# ProPrj_ftdi-jtag-xilinx_2025-03-20_v3_2.net
KiCad netlist of a schematic drawn in EasyEDA Pro
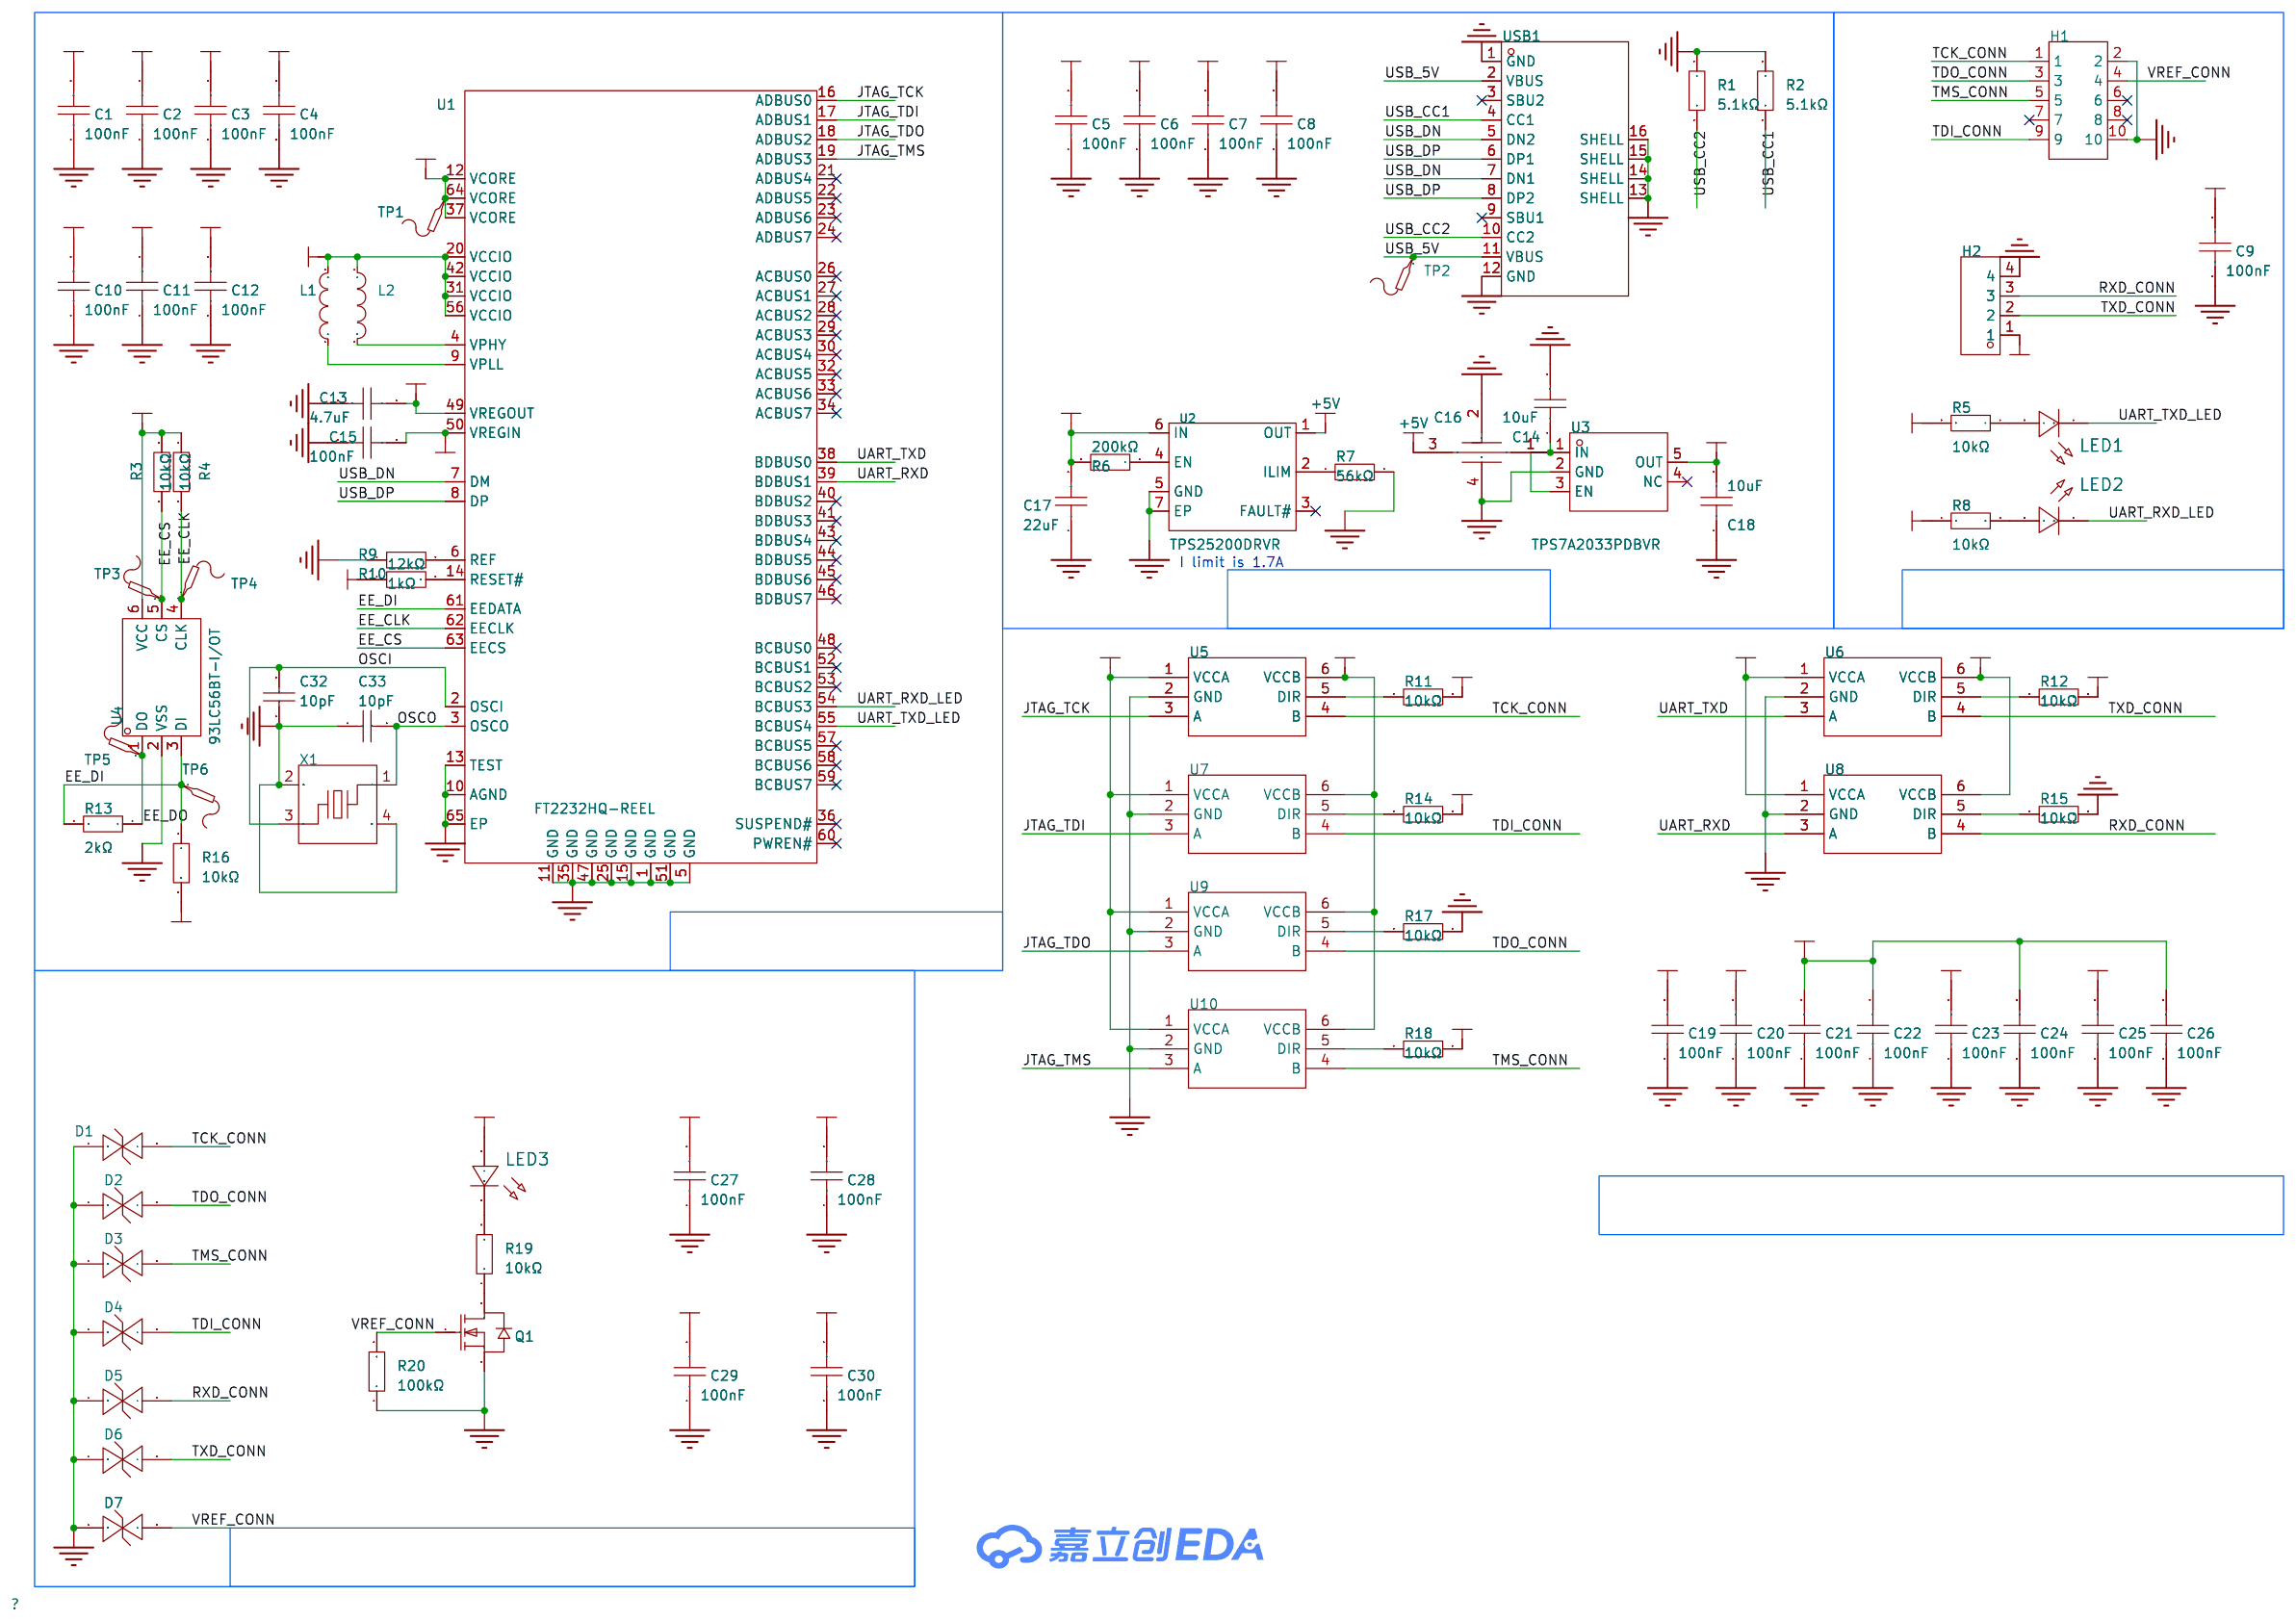
[diagram p0: schematic sheet]

(export (version "E")
  (design (tool "Eeschema 10.0.6"))
  (components
    (comp (ref "C1")
      (value "100nF")
      (footprint "easyedapro:C0603")
      (fields
        (field (name "Manufacturer Part") "CC0402KRX7R7BB104")
        (field (name "Manufacturer") "YAGEO(国巨)")
      )
      (libsource (lib "easyedapro") (part "CapAcitance"))
    )
    (comp (ref "C2")
      (value "100nF")
      (footprint "easyedapro:C0603")
      (fields
        (field (name "Manufacturer Part") "CC0402KRX7R7BB104")
        (field (name "Manufacturer") "YAGEO(国巨)")
      )
      (libsource (lib "easyedapro") (part "CapAcitance"))
    )
    (comp (ref "C3")
      (value "100nF")
      (footprint "easyedapro:C0603")
      (fields
        (field (name "Manufacturer Part") "CC0402KRX7R7BB104")
        (field (name "Manufacturer") "YAGEO(国巨)")
      )
      (libsource (lib "easyedapro") (part "CapAcitance"))
    )
    (comp (ref "C4")
      (value "100nF")
      (footprint "easyedapro:C0603")
      (fields
        (field (name "Manufacturer Part") "CC0402KRX7R7BB104")
        (field (name "Manufacturer") "YAGEO(国巨)")
      )
      (libsource (lib "easyedapro") (part "CapAcitance"))
    )
    (comp (ref "C5")
      (value "100nF")
      (footprint "easyedapro:C0603")
      (fields
        (field (name "Manufacturer Part") "CC0402KRX7R7BB104")
        (field (name "Manufacturer") "YAGEO(国巨)")
      )
      (libsource (lib "easyedapro") (part "CapAcitance"))
    )
    (comp (ref "C6")
      (value "100nF")
      (footprint "easyedapro:C0603")
      (fields
        (field (name "Manufacturer Part") "CC0402KRX7R7BB104")
        (field (name "Manufacturer") "YAGEO(国巨)")
      )
      (libsource (lib "easyedapro") (part "CapAcitance"))
    )
    (comp (ref "C7")
      (value "100nF")
      (footprint "easyedapro:C0603")
      (fields
        (field (name "Manufacturer Part") "CC0402KRX7R7BB104")
        (field (name "Manufacturer") "YAGEO(国巨)")
      )
      (libsource (lib "easyedapro") (part "CapAcitance"))
    )
    (comp (ref "C8")
      (value "100nF")
      (footprint "easyedapro:C0603")
      (fields
        (field (name "Manufacturer Part") "CC0402KRX7R7BB104")
        (field (name "Manufacturer") "YAGEO(国巨)")
      )
      (libsource (lib "easyedapro") (part "CapAcitance"))
    )
    (comp (ref "C9")
      (value "100nF")
      (footprint "easyedapro:C0603")
      (fields
        (field (name "Manufacturer Part") "CC0402KRX7R7BB104")
        (field (name "Manufacturer") "YAGEO(国巨)")
      )
      (libsource (lib "easyedapro") (part "CapAcitance"))
    )
    (comp (ref "C10")
      (value "100nF")
      (footprint "easyedapro:C0603")
      (fields
        (field (name "Manufacturer Part") "CC0402KRX7R7BB104")
        (field (name "Manufacturer") "YAGEO(国巨)")
      )
      (libsource (lib "easyedapro") (part "CapAcitance"))
    )
    (comp (ref "C11")
      (value "100nF")
      (footprint "easyedapro:C0603")
      (fields
        (field (name "Manufacturer Part") "CC0402KRX7R7BB104")
        (field (name "Manufacturer") "YAGEO(国巨)")
      )
      (libsource (lib "easyedapro") (part "CapAcitance"))
    )
    (comp (ref "C12")
      (value "100nF")
      (footprint "easyedapro:C0603")
      (fields
        (field (name "Manufacturer Part") "CC0402KRX7R7BB104")
        (field (name "Manufacturer") "YAGEO(国巨)")
      )
      (libsource (lib "easyedapro") (part "CapAcitance"))
    )
    (comp (ref "C13")
      (value "4.7uF")
      (footprint "easyedapro:C0603")
      (fields
        (field (name "Manufacturer Part") "CL05A475KP5NRNC")
        (field (name "Manufacturer") "SAMSUNG(三星)")
      )
      (libsource (lib "easyedapro") (part "CapAcitance"))
    )
    (comp (ref "C14")
      (value "10uF")
      (footprint "easyedapro:C0603")
      (fields
        (field (name "Manufacturer Part") "CL10A106MA8NRNC")
        (field (name "Manufacturer") "SAMSUNG(三星)")
      )
      (libsource (lib "easyedapro") (part "CapAcitance"))
    )
    (comp (ref "C15")
      (value "100nF")
      (footprint "easyedapro:C0603")
      (fields
        (field (name "Manufacturer Part") "CC0402KRX7R7BB104")
        (field (name "Manufacturer") "YAGEO(国巨)")
      )
      (libsource (lib "easyedapro") (part "CapAcitance"))
    )
    (comp (ref "C16")
      (value "NFM21PC104R1E3D")
      (footprint "easyedapro:CAP-SMD_4P-L2.0-W1.25")
      (description "电容量:100nF;精度:±20%;直流电阻:30mΩ;")
      (fields (field (name "Manufacturer") "muRata(村田)"))
      (libsource (lib "easyedapro") (part "NFM21PC104R1E3D"))
    )
    (comp (ref "C17")
      (value "22uF")
      (footprint "easyedapro:C0603")
      (fields
        (field (name "Manufacturer Part") "CGA0805X5R226M350MT")
        (field (name "Manufacturer") "HRE(芯声)")
      )
      (libsource (lib "easyedapro") (part "CapAcitance"))
    )
    (comp (ref "C18")
      (value "10uF")
      (footprint "easyedapro:C0603")
      (fields
        (field (name "Manufacturer Part") "CL10A106MA8NRNC")
        (field (name "Manufacturer") "SAMSUNG(三星)")
      )
      (libsource (lib "easyedapro") (part "CapAcitance"))
    )
    (comp (ref "C19")
      (value "100nF")
      (footprint "easyedapro:C0603")
      (fields
        (field (name "Manufacturer Part") "CC0402KRX7R7BB104")
        (field (name "Manufacturer") "YAGEO(国巨)")
      )
      (libsource (lib "easyedapro") (part "CapAcitance"))
    )
    (comp (ref "C20")
      (value "100nF")
      (footprint "easyedapro:C0603")
      (fields
        (field (name "Manufacturer Part") "CC0402KRX7R7BB104")
        (field (name "Manufacturer") "YAGEO(国巨)")
      )
      (libsource (lib "easyedapro") (part "CapAcitance"))
    )
    (comp (ref "C21")
      (value "100nF")
      (footprint "easyedapro:C0603")
      (fields
        (field (name "Manufacturer Part") "CC0402KRX7R7BB104")
        (field (name "Manufacturer") "YAGEO(国巨)")
      )
      (libsource (lib "easyedapro") (part "CapAcitance"))
    )
    (comp (ref "C22")
      (value "100nF")
      (footprint "easyedapro:C0603")
      (fields
        (field (name "Manufacturer Part") "CC0402KRX7R7BB104")
        (field (name "Manufacturer") "YAGEO(国巨)")
      )
      (libsource (lib "easyedapro") (part "CapAcitance"))
    )
    (comp (ref "C23")
      (value "100nF")
      (footprint "easyedapro:C0603")
      (fields
        (field (name "Manufacturer Part") "CC0402KRX7R7BB104")
        (field (name "Manufacturer") "YAGEO(国巨)")
      )
      (libsource (lib "easyedapro") (part "CapAcitance"))
    )
    (comp (ref "C24")
      (value "100nF")
      (footprint "easyedapro:C0603")
      (fields
        (field (name "Manufacturer Part") "CC0402KRX7R7BB104")
        (field (name "Manufacturer") "YAGEO(国巨)")
      )
      (libsource (lib "easyedapro") (part "CapAcitance"))
    )
    (comp (ref "C25")
      (value "100nF")
      (footprint "easyedapro:C0603")
      (fields
        (field (name "Manufacturer Part") "CC0402KRX7R7BB104")
        (field (name "Manufacturer") "YAGEO(国巨)")
      )
      (libsource (lib "easyedapro") (part "CapAcitance"))
    )
    (comp (ref "C26")
      (value "100nF")
      (footprint "easyedapro:C0603")
      (fields
        (field (name "Manufacturer Part") "CC0402KRX7R7BB104")
        (field (name "Manufacturer") "YAGEO(国巨)")
      )
      (libsource (lib "easyedapro") (part "CapAcitance"))
    )
    (comp (ref "C27")
      (value "100nF")
      (footprint "easyedapro:C0603")
      (fields
        (field (name "Manufacturer Part") "CC0402KRX7R7BB104")
        (field (name "Manufacturer") "YAGEO(国巨)")
      )
      (libsource (lib "easyedapro") (part "CapAcitance"))
    )
    (comp (ref "C28")
      (value "100nF")
      (footprint "easyedapro:C0603")
      (fields
        (field (name "Manufacturer Part") "CC0402KRX7R7BB104")
        (field (name "Manufacturer") "YAGEO(国巨)")
      )
      (libsource (lib "easyedapro") (part "CapAcitance"))
    )
    (comp (ref "C29")
      (value "100nF")
      (footprint "easyedapro:C0603")
      (fields
        (field (name "Manufacturer Part") "CC0402KRX7R7BB104")
        (field (name "Manufacturer") "YAGEO(国巨)")
      )
      (libsource (lib "easyedapro") (part "CapAcitance"))
    )
    (comp (ref "C30")
      (value "100nF")
      (footprint "easyedapro:C0603")
      (fields
        (field (name "Manufacturer Part") "CC0402KRX7R7BB104")
        (field (name "Manufacturer") "YAGEO(国巨)")
      )
      (libsource (lib "easyedapro") (part "CapAcitance"))
    )
    (comp (ref "C32")
      (value "10pF")
      (footprint "easyedapro:C0402")
      (description "容值:10pF;精度:±5%;额定电压:50V;材质(温度系数):NP0;")
      (fields
        (field (name "Manufacturer Part") "CC0402JRNPO9BN100")
        (field (name "Manufacturer") "YAGEO(国巨)")
      )
      (libsource (lib "easyedapro") (part "CC0402JRNPO9BN100"))
    )
    (comp (ref "C33")
      (value "10pF")
      (footprint "easyedapro:C0402")
      (description "容值:10pF;精度:±5%;额定电压:50V;材质(温度系数):NP0;")
      (fields
        (field (name "Manufacturer Part") "CC0402JRNPO9BN100")
        (field (name "Manufacturer") "YAGEO(国巨)")
      )
      (libsource (lib "easyedapro") (part "CC0402JRNPO9BN100"))
    )
    (comp (ref "D1")
      (value "H5VL10B")
      (footprint "easyedapro:SOD-882_L1.0-W0.6-BI")
      (description "极性:双向;反向截止电压(Vrwm):5V;最大钳位电压:10V;峰值脉冲电流(Ipp):5A;峰值脉冲功率(Ppp):50W;击穿电压:5.6V;")
      (fields (field (name "Manufacturer") "宏迦橙"))
      (libsource (lib "easyedapro") (part "H5VL10B"))
    )
    (comp (ref "D2")
      (value "H5VL10B")
      (footprint "easyedapro:SOD-882_L1.0-W0.6-BI")
      (description "极性:双向;反向截止电压(Vrwm):5V;最大钳位电压:10V;峰值脉冲电流(Ipp):5A;峰值脉冲功率(Ppp):50W;击穿电压:5.6V;")
      (fields (field (name "Manufacturer") "宏迦橙"))
      (libsource (lib "easyedapro") (part "H5VL10B"))
    )
    (comp (ref "D3")
      (value "H5VL10B")
      (footprint "easyedapro:SOD-882_L1.0-W0.6-BI")
      (description "极性:双向;反向截止电压(Vrwm):5V;最大钳位电压:10V;峰值脉冲电流(Ipp):5A;峰值脉冲功率(Ppp):50W;击穿电压:5.6V;")
      (fields (field (name "Manufacturer") "宏迦橙"))
      (libsource (lib "easyedapro") (part "H5VL10B"))
    )
    (comp (ref "D4")
      (value "H5VL10B")
      (footprint "easyedapro:SOD-882_L1.0-W0.6-BI")
      (description "极性:双向;反向截止电压(Vrwm):5V;最大钳位电压:10V;峰值脉冲电流(Ipp):5A;峰值脉冲功率(Ppp):50W;击穿电压:5.6V;")
      (fields (field (name "Manufacturer") "宏迦橙"))
      (libsource (lib "easyedapro") (part "H5VL10B"))
    )
    (comp (ref "D5")
      (value "H5VL10B")
      (footprint "easyedapro:SOD-882_L1.0-W0.6-BI")
      (description "极性:双向;反向截止电压(Vrwm):5V;最大钳位电压:10V;峰值脉冲电流(Ipp):5A;峰值脉冲功率(Ppp):50W;击穿电压:5.6V;")
      (fields (field (name "Manufacturer") "宏迦橙"))
      (libsource (lib "easyedapro") (part "H5VL10B"))
    )
    (comp (ref "D6")
      (value "H5VL10B")
      (footprint "easyedapro:SOD-882_L1.0-W0.6-BI")
      (description "极性:双向;反向截止电压(Vrwm):5V;最大钳位电压:10V;峰值脉冲电流(Ipp):5A;峰值脉冲功率(Ppp):50W;击穿电压:5.6V;")
      (fields (field (name "Manufacturer") "宏迦橙"))
      (libsource (lib "easyedapro") (part "H5VL10B"))
    )
    (comp (ref "D7")
      (value "H5VL10B")
      (footprint "easyedapro:SOD-882_L1.0-W0.6-BI")
      (description "极性:双向;反向截止电压(Vrwm):5V;最大钳位电压:10V;峰值脉冲电流(Ipp):5A;峰值脉冲功率(Ppp):50W;击穿电压:5.6V;")
      (fields (field (name "Manufacturer") "宏迦橙"))
      (libsource (lib "easyedapro") (part "H5VL10B"))
    )
    (comp (ref "H1")
      (value "PZ254-2-05-Z-8.5")
      (footprint "easyedapro:HDR-TH_10P-P2.54-V-M-R2-C5-S2.54")
      (fields (field (name "Manufacturer") "HCTL(华灿天禄)"))
      (libsource (lib "easyedapro") (part "PZ254-2-05-Z-8.5"))
    )
    (comp (ref "H2")
      (value "PZ254V-11-04P")
      (footprint "easyedapro:HDR-TH_4P-P2.54-V-M")
      (fields (field (name "Manufacturer") "XFCN(兴飞)"))
      (libsource (lib "easyedapro") (part "PZ254V-11-04P_C2691448"))
    )
    (comp (ref "L1")
      (value "BLM15PD121SN1D")
      (footprint "easyedapro:L0402")
      (description "标称阻抗@测试频率:120Ω@100MHz;误差:±25%;直流电阻(RDC):90mΩ;")
      (fields (field (name "Manufacturer") "muRata(村田)"))
      (libsource (lib "easyedapro") (part "BLM15PD121SN1D"))
    )
    (comp (ref "L2")
      (value "BLM15PD121SN1D")
      (footprint "easyedapro:L0402")
      (description "标称阻抗@测试频率:120Ω@100MHz;误差:±25%;直流电阻(RDC):90mΩ;")
      (fields (field (name "Manufacturer") "muRata(村田)"))
      (libsource (lib "easyedapro") (part "BLM15PD121SN1D"))
    )
    (comp (ref "LED1")
      (value "NCD0603Y1")
      (footprint "easyedapro:LED_0603")
      (fields (field (name "Manufacturer") "国星光电"))
      (libsource (lib "easyedapro") (part "LED_R"))
    )
    (comp (ref "LED2")
      (value "NCD0603Y1")
      (footprint "easyedapro:LED_0603")
      (fields (field (name "Manufacturer") "国星光电"))
      (libsource (lib "easyedapro") (part "LED_R"))
    )
    (comp (ref "LED3")
      (value "NCD0603Y1")
      (footprint "easyedapro:LED_0603")
      (fields (field (name "Manufacturer") "国星光电"))
      (libsource (lib "easyedapro") (part "LED_R"))
    )
    (comp (ref "Q1")
      (value "SI2302")
      (footprint "easyedapro:SOT-23-3_L2.9-W1.3-P1.90-LS2.4-BR")
      (description "类型:1个N沟道;漏源电压(Vdss):20V;连续漏极电流(Id):3A;导通电阻(RDS(on)):50mΩ@4.5V,3A;耗散功率(Pd):1W;阈值电压(Vgs(th)):1V;")
      (fields (field (name "Manufacturer") "YONGYUTAI(永裕泰)"))
      (libsource (lib "easyedapro") (part "SI2302_C2891732"))
    )
    (comp (ref "R1")
      (value "5.1kΩ")
      (footprint "easyedapro:R0603")
      (fields
        (field (name "Manufacturer Part") "0402WGF5101TCE")
        (field (name "Manufacturer") "UNI-ROYAL(厚声)")
      )
      (libsource (lib "easyedapro") (part "电阻"))
    )
    (comp (ref "R2")
      (value "5.1kΩ")
      (footprint "easyedapro:R0603")
      (fields
        (field (name "Manufacturer Part") "0402WGF5101TCE")
        (field (name "Manufacturer") "UNI-ROYAL(厚声)")
      )
      (libsource (lib "easyedapro") (part "电阻"))
    )
    (comp (ref "R3")
      (value "10kΩ")
      (footprint "easyedapro:R0603")
      (fields (field (name "Manufacturer Part") "RC0402FR-0710KL") (field (name "Manufacturer") "YAGEO(国巨)"))
      (libsource (lib "easyedapro") (part "电阻"))
    )
    (comp (ref "R4")
      (value "10kΩ")
      (footprint "easyedapro:R0603")
      (fields (field (name "Manufacturer Part") "RC0402FR-0710KL") (field (name "Manufacturer") "YAGEO(国巨)"))
      (libsource (lib "easyedapro") (part "电阻"))
    )
    (comp (ref "R5")
      (value "10kΩ")
      (footprint "easyedapro:R0603")
      (fields (field (name "Manufacturer Part") "RC0402FR-0710KL") (field (name "Manufacturer") "YAGEO(国巨)"))
      (libsource (lib "easyedapro") (part "电阻"))
    )
    (comp (ref "R6")
      (value "200kΩ")
      (footprint "easyedapro:R0603")
      (fields
        (field (name "Manufacturer Part") "0402WGF2003TCE")
        (field (name "Manufacturer") "UNI-ROYAL(厚声)")
      )
      (libsource (lib "easyedapro") (part "电阻"))
    )
    (comp (ref "R7")
      (value "56kΩ")
      (footprint "easyedapro:R0603")
      (fields
        (field (name "Manufacturer Part") "0402WGF5602TCE")
        (field (name "Manufacturer") "UNI-ROYAL(厚声)")
      )
      (libsource (lib "easyedapro") (part "电阻"))
    )
    (comp (ref "R8")
      (value "10kΩ")
      (footprint "easyedapro:R0603")
      (fields (field (name "Manufacturer Part") "RC0402FR-0710KL") (field (name "Manufacturer") "YAGEO(国巨)"))
      (libsource (lib "easyedapro") (part "电阻"))
    )
    (comp (ref "R9")
      (value "12kΩ")
      (footprint "easyedapro:R0603")
      (fields
        (field (name "Manufacturer Part") "0402WGF1202TCE")
        (field (name "Manufacturer") "UNI-ROYAL(厚声)")
      )
      (libsource (lib "easyedapro") (part "电阻"))
    )
    (comp (ref "R10")
      (value "1kΩ")
      (footprint "easyedapro:R0603")
      (fields
        (field (name "Manufacturer Part") "0402WGF1001TCE")
        (field (name "Manufacturer") "UNI-ROYAL(厚声)")
      )
      (libsource (lib "easyedapro") (part "电阻"))
    )
    (comp (ref "R11")
      (value "10kΩ")
      (footprint "easyedapro:R0603")
      (fields (field (name "Manufacturer Part") "RC0402FR-0710KL") (field (name "Manufacturer") "YAGEO(国巨)"))
      (libsource (lib "easyedapro") (part "电阻"))
    )
    (comp (ref "R12")
      (value "10kΩ")
      (footprint "easyedapro:R0603")
      (fields (field (name "Manufacturer Part") "RC0402FR-0710KL") (field (name "Manufacturer") "YAGEO(国巨)"))
      (libsource (lib "easyedapro") (part "电阻"))
    )
    (comp (ref "R13")
      (value "2kΩ")
      (footprint "easyedapro:R0603")
      (fields (field (name "Manufacturer Part") "FRC0402F2001TS") (field (name "Manufacturer") "FOJAN(富捷)"))
      (libsource (lib "easyedapro") (part "电阻"))
    )
    (comp (ref "R14")
      (value "10kΩ")
      (footprint "easyedapro:R0603")
      (fields (field (name "Manufacturer Part") "RC0402FR-0710KL") (field (name "Manufacturer") "YAGEO(国巨)"))
      (libsource (lib "easyedapro") (part "电阻"))
    )
    (comp (ref "R15")
      (value "10kΩ")
      (footprint "easyedapro:R0603")
      (fields (field (name "Manufacturer Part") "RC0402FR-0710KL") (field (name "Manufacturer") "YAGEO(国巨)"))
      (libsource (lib "easyedapro") (part "电阻"))
    )
    (comp (ref "R16")
      (value "10kΩ")
      (footprint "easyedapro:R0603")
      (fields (field (name "Manufacturer Part") "RC0402FR-0710KL") (field (name "Manufacturer") "YAGEO(国巨)"))
      (libsource (lib "easyedapro") (part "电阻"))
    )
    (comp (ref "R17")
      (value "10kΩ")
      (footprint "easyedapro:R0603")
      (fields (field (name "Manufacturer Part") "RC0402FR-0710KL") (field (name "Manufacturer") "YAGEO(国巨)"))
      (libsource (lib "easyedapro") (part "电阻"))
    )
    (comp (ref "R18")
      (value "10kΩ")
      (footprint "easyedapro:R0603")
      (fields (field (name "Manufacturer Part") "RC0402FR-0710KL") (field (name "Manufacturer") "YAGEO(国巨)"))
      (libsource (lib "easyedapro") (part "电阻"))
    )
    (comp (ref "R19")
      (value "10kΩ")
      (footprint "easyedapro:R0603")
      (fields (field (name "Manufacturer Part") "RC0402FR-0710KL") (field (name "Manufacturer") "YAGEO(国巨)"))
      (libsource (lib "easyedapro") (part "电阻"))
    )
    (comp (ref "R20")
      (value "100kΩ")
      (footprint "easyedapro:R0402")
      (description "电阻类型:厚膜电阻;阻值:100kΩ;精度:±1%;功率:62.5mW;最大工作电压:50V;温度系数:±100ppm/°C;")
      (fields
        (field (name "Manufacturer Part") "0402WGF1003TCE")
        (field (name "Manufacturer") "UNI-ROYAL(厚声)")
      )
      (libsource (lib "easyedapro") (part "0402WGF1003TCE"))
    )
    (comp (ref "TP1")
      (value "~")
      (footprint "easyedapro:Test-Point-0.5mm")
      (description "Test Point 测试点")
      (libsource (lib "easyedapro") (part "Test-Point"))
    )
    (comp (ref "TP2")
      (value "~")
      (footprint "easyedapro:Test-Point-0.5mm")
      (description "Test Point 测试点")
      (libsource (lib "easyedapro") (part "Test-Point"))
    )
    (comp (ref "TP3")
      (value "~")
      (footprint "easyedapro:Test-Point-0.5mm")
      (description "Test Point 测试点")
      (libsource (lib "easyedapro") (part "Test-Point"))
    )
    (comp (ref "TP4")
      (value "~")
      (footprint "easyedapro:Test-Point-0.5mm")
      (description "Test Point 测试点")
      (libsource (lib "easyedapro") (part "Test-Point"))
    )
    (comp (ref "TP5")
      (value "~")
      (footprint "easyedapro:Test-Point-0.5mm")
      (description "Test Point 测试点")
      (libsource (lib "easyedapro") (part "Test-Point"))
    )
    (comp (ref "TP6")
      (value "~")
      (footprint "easyedapro:Test-Point-0.5mm")
      (description "Test Point 测试点")
      (libsource (lib "easyedapro") (part "Test-Point"))
    )
    (comp (ref "U1")
      (value "FT2232HQ-REEL")
      (footprint "easyedapro:QFN-64_L9.0-W9.0-P0.50-TL-EP4.3")
      (description "应用功能:USB转UART；USB转FIFO;接口协议:UART;供电电压:3V~3.6V;")
      (fields (field (name "Manufacturer") "FTDI(飞特帝亚)"))
      (libsource (lib "easyedapro") (part "FT2232HQ-REEL"))
    )
    (comp (ref "U2")
      (value "TPS25200DRVR")
      (footprint "easyedapro:WSON-6_L2.0-W2.0-P0.65-TL-EP")
      (description "TPS25200 具有过压钳位的 6.5V/2.8A 电子保险丝")
      (fields (field (name "Manufacturer") "TI(德州仪器)"))
      (libsource (lib "easyedapro") (part "TPS25200DRVR"))
    )
    (comp (ref "U3")
      (value "TPS7A2033PDBVR")
      (footprint "easyedapro:SOT-23-5_L2.9-W1.6-P0.95-LS2.8-BR")
      (fields (field (name "Manufacturer") "TI(德州仪器)"))
      (libsource (lib "easyedapro") (part "TPS7A2033PDBVR"))
    )
    (comp (ref "U4")
      (value "93LC56BT-I/OT")
      (footprint "easyedapro:SOT-23-6_L2.9-W1.6-P0.95-LS2.8-BR")
      (fields (field (name "Manufacturer") "MICROCHIP(美国微芯)"))
      (libsource (lib "easyedapro") (part "93LC56BT-I/OT"))
    )
    (comp (ref "U5")
      (value "SN74LVC1T45DBVR")
      (footprint "easyedapro:SOT-23-6_L2.9-W1.6-P0.95-LS2.8-BR")
      (description "数据速率:420Mbps;电压(VCCA):1.65V~5.5V;电压(VCCB):1.65V~5.5V;电路数:1;每个电路通道数:1;")
      (fields (field (name "Manufacturer") "TI(德州仪器)"))
      (libsource (lib "easyedapro") (part "SN74LVC1T45DBVR"))
    )
    (comp (ref "U6")
      (value "SN74LVC1T45DBVR")
      (footprint "easyedapro:SOT-23-6_L2.9-W1.6-P0.95-LS2.8-BR")
      (description "数据速率:420Mbps;电压(VCCA):1.65V~5.5V;电压(VCCB):1.65V~5.5V;电路数:1;每个电路通道数:1;")
      (fields (field (name "Manufacturer") "TI(德州仪器)"))
      (libsource (lib "easyedapro") (part "SN74LVC1T45DBVR"))
    )
    (comp (ref "U7")
      (value "SN74LVC1T45DBVR")
      (footprint "easyedapro:SOT-23-6_L2.9-W1.6-P0.95-LS2.8-BR")
      (description "数据速率:420Mbps;电压(VCCA):1.65V~5.5V;电压(VCCB):1.65V~5.5V;电路数:1;每个电路通道数:1;")
      (fields (field (name "Manufacturer") "TI(德州仪器)"))
      (libsource (lib "easyedapro") (part "SN74LVC1T45DBVR"))
    )
    (comp (ref "U8")
      (value "SN74LVC1T45DBVR")
      (footprint "easyedapro:SOT-23-6_L2.9-W1.6-P0.95-LS2.8-BR")
      (description "数据速率:420Mbps;电压(VCCA):1.65V~5.5V;电压(VCCB):1.65V~5.5V;电路数:1;每个电路通道数:1;")
      (fields (field (name "Manufacturer") "TI(德州仪器)"))
      (libsource (lib "easyedapro") (part "SN74LVC1T45DBVR"))
    )
    (comp (ref "U9")
      (value "SN74LVC1T45DBVR")
      (footprint "easyedapro:SOT-23-6_L2.9-W1.6-P0.95-LS2.8-BR")
      (description "数据速率:420Mbps;电压(VCCA):1.65V~5.5V;电压(VCCB):1.65V~5.5V;电路数:1;每个电路通道数:1;")
      (fields (field (name "Manufacturer") "TI(德州仪器)"))
      (libsource (lib "easyedapro") (part "SN74LVC1T45DBVR"))
    )
    (comp (ref "U10")
      (value "SN74LVC1T45DBVR")
      (footprint "easyedapro:SOT-23-6_L2.9-W1.6-P0.95-LS2.8-BR")
      (description "数据速率:420Mbps;电压(VCCA):1.65V~5.5V;电压(VCCB):1.65V~5.5V;电路数:1;每个电路通道数:1;")
      (fields (field (name "Manufacturer") "TI(德州仪器)"))
      (libsource (lib "easyedapro") (part "SN74LVC1T45DBVR"))
    )
    (comp (ref "USB1")
      (value "TYPEC-302-BRP16SC16")
      (footprint "easyedapro:USB-C-SMD_TYPEC-302-BRP16SC16")
      (fields (field (name "Manufacturer") "XUNPU(讯普)"))
      (libsource (lib "easyedapro") (part "TYPEC-302-BRP16SC16"))
    )
    (comp (ref "X1")
      (value "12MHz")
      (footprint "easyedapro:CRYSTAL-SMD_4P-L2.5-W2.0-BL-A")
      (description "晶振类型:贴片晶振;频率:12MHz;常温频差:±10ppm;负载电容:10pF;频率稳定度:±20ppm;")
      (fields (field (name "Manufacturer Part") "X252012MMB4SI-24") (field (name "Manufacturer") "YXC(扬兴晶振)"))
      (libsource (lib "easyedapro") (part "X252012MMB4SI-24"))
    )
  )
  (nets
    (net (code "1") (name "+5V") (class "Default")
      (node (ref "C16") (pin "3") (pinfunction "OUT_3") (pintype "input"))
      (node (ref "U2") (pin "1") (pinfunction "OUT_1") (pintype "input"))
    )
    (net (code "2") (name "/EE_CLK") (class "Default")
      (node (ref "R4") (pin "2") (pinfunction "2_2") (pintype "input"))
      (node (ref "TP4") (pin "1") (pinfunction "1_1") (pintype "input"))
      (node (ref "U1") (pin "62") (pinfunction "EECLK_62") (pintype "input"))
      (node (ref "U4") (pin "4") (pinfunction "CLK_4") (pintype "input"))
    )
    (net (code "3") (name "/EE_CS") (class "Default")
      (node (ref "R3") (pin "2") (pinfunction "2_2") (pintype "input"))
      (node (ref "TP3") (pin "1") (pinfunction "1_1") (pintype "input"))
      (node (ref "U1") (pin "63") (pinfunction "EECS_63") (pintype "input"))
      (node (ref "U4") (pin "5") (pinfunction "CS_5") (pintype "input"))
    )
    (net (code "4") (name "/EE_DI") (class "Default")
      (node (ref "R13") (pin "2") (pinfunction "2_2") (pintype "input"))
      (node (ref "R16") (pin "1") (pinfunction "1_1") (pintype "input"))
      (node (ref "TP6") (pin "1") (pinfunction "1_1") (pintype "input"))
      (node (ref "U1") (pin "61") (pinfunction "EEDATA_61") (pintype "input"))
      (node (ref "U4") (pin "3") (pinfunction "DI_3") (pintype "input"))
    )
    (net (code "5") (name "/EE_DO") (class "Default")
      (node (ref "R13") (pin "1") (pinfunction "1_1") (pintype "input"))
      (node (ref "TP5") (pin "1") (pinfunction "1_1") (pintype "input"))
      (node (ref "U4") (pin "1") (pinfunction "DO_1") (pintype "input"))
    )
    (net (code "6") (name "/JTAG_TCK") (class "Default")
      (node (ref "U1") (pin "16") (pinfunction "ADBUS0_16") (pintype "input"))
      (node (ref "U5") (pin "3") (pinfunction "A_3") (pintype "unspecified"))
    )
    (net (code "7") (name "/JTAG_TDI") (class "Default")
      (node (ref "U1") (pin "17") (pinfunction "ADBUS1_17") (pintype "input"))
      (node (ref "U7") (pin "3") (pinfunction "A_3") (pintype "unspecified"))
    )
    (net (code "8") (name "/JTAG_TDO") (class "Default")
      (node (ref "U1") (pin "18") (pinfunction "ADBUS2_18") (pintype "input"))
      (node (ref "U9") (pin "3") (pinfunction "A_3") (pintype "unspecified"))
    )
    (net (code "9") (name "/JTAG_TMS") (class "Default")
      (node (ref "U1") (pin "19") (pinfunction "ADBUS3_19") (pintype "input"))
      (node (ref "U10") (pin "3") (pinfunction "A_3") (pintype "unspecified"))
    )
    (net (code "10") (name "/OSCI") (class "Default")
      (node (ref "C32") (pin "2") (pinfunction "2_2") (pintype "input"))
      (node (ref "U1") (pin "2") (pinfunction "OSCI_2") (pintype "input"))
      (node (ref "X1") (pin "3") (pinfunction "3_3") (pintype "input"))
    )
    (net (code "11") (name "/OSCO") (class "Default")
      (node (ref "C33") (pin "2") (pinfunction "2_2") (pintype "input"))
      (node (ref "U1") (pin "3") (pinfunction "OSCO_3") (pintype "input"))
      (node (ref "X1") (pin "1") (pinfunction "1_1") (pintype "input"))
    )
    (net (code "12") (name "/RXD_CONN") (class "Default")
      (node (ref "D5") (pin "2") (pinfunction "A_2") (pintype "unspecified"))
      (node (ref "H2") (pin "3") (pinfunction "3_3") (pintype "unspecified"))
      (node (ref "U8") (pin "4") (pinfunction "B_4") (pintype "unspecified"))
    )
    (net (code "13") (name "/TCK_CONN") (class "Default")
      (node (ref "D1") (pin "2") (pinfunction "A_2") (pintype "unspecified"))
      (node (ref "H1") (pin "1") (pinfunction "1_1") (pintype "unspecified"))
      (node (ref "U5") (pin "4") (pinfunction "B_4") (pintype "unspecified"))
    )
    (net (code "14") (name "/TDI_CONN") (class "Default")
      (node (ref "D4") (pin "2") (pinfunction "A_2") (pintype "unspecified"))
      (node (ref "H1") (pin "9") (pinfunction "9_9") (pintype "unspecified"))
      (node (ref "U7") (pin "4") (pinfunction "B_4") (pintype "unspecified"))
    )
    (net (code "15") (name "/TDO_CONN") (class "Default")
      (node (ref "D2") (pin "2") (pinfunction "A_2") (pintype "unspecified"))
      (node (ref "H1") (pin "3") (pinfunction "3_3") (pintype "unspecified"))
      (node (ref "U9") (pin "4") (pinfunction "B_4") (pintype "unspecified"))
    )
    (net (code "16") (name "/TMS_CONN") (class "Default")
      (node (ref "D3") (pin "2") (pinfunction "A_2") (pintype "unspecified"))
      (node (ref "H1") (pin "5") (pinfunction "5_5") (pintype "unspecified"))
      (node (ref "U10") (pin "4") (pinfunction "B_4") (pintype "unspecified"))
    )
    (net (code "17") (name "/TXD_CONN") (class "Default")
      (node (ref "D6") (pin "2") (pinfunction "A_2") (pintype "unspecified"))
      (node (ref "H2") (pin "2") (pinfunction "2_2") (pintype "unspecified"))
      (node (ref "U6") (pin "4") (pinfunction "B_4") (pintype "unspecified"))
    )
    (net (code "18") (name "/UART_RXD") (class "Default")
      (node (ref "U1") (pin "39") (pinfunction "BDBUS1_39") (pintype "input"))
      (node (ref "U8") (pin "3") (pinfunction "A_3") (pintype "unspecified"))
    )
    (net (code "19") (name "/UART_RXD_LED") (class "Default")
      (node (ref "LED2") (pin "1") (pinfunction "C_1") (pintype "input"))
      (node (ref "U1") (pin "54") (pinfunction "BCBUS3_54") (pintype "input"))
    )
    (net (code "20") (name "/UART_TXD") (class "Default")
      (node (ref "U1") (pin "38") (pinfunction "BDBUS0_38") (pintype "input"))
      (node (ref "U6") (pin "3") (pinfunction "A_3") (pintype "unspecified"))
    )
    (net (code "21") (name "/UART_TXD_LED") (class "Default")
      (node (ref "LED1") (pin "1") (pinfunction "C_1") (pintype "input"))
      (node (ref "U1") (pin "55") (pinfunction "BCBUS4_55") (pintype "input"))
    )
    (net (code "22") (name "/USB_CC1") (class "Default")
      (node (ref "R2") (pin "2") (pinfunction "2_2") (pintype "input"))
      (node (ref "USB1") (pin "4") (pinfunction "CC1_4") (pintype "unspecified"))
    )
    (net (code "23") (name "/USB_CC2") (class "Default")
      (node (ref "R1") (pin "2") (pinfunction "2_2") (pintype "input"))
      (node (ref "USB1") (pin "10") (pinfunction "CC2_10") (pintype "unspecified"))
    )
    (net (code "24") (name "/USB_DN") (class "Default")
      (node (ref "U1") (pin "7") (pinfunction "DM_7") (pintype "input"))
      (node (ref "USB1") (pin "5") (pinfunction "DN2_5") (pintype "unspecified"))
      (node (ref "USB1") (pin "7") (pinfunction "DN1_7") (pintype "unspecified"))
    )
    (net (code "25") (name "/USB_DP") (class "Default")
      (node (ref "U1") (pin "8") (pinfunction "DP_8") (pintype "input"))
      (node (ref "USB1") (pin "6") (pinfunction "DP1_6") (pintype "unspecified"))
      (node (ref "USB1") (pin "8") (pinfunction "DP2_8") (pintype "unspecified"))
    )
    (net (code "26") (name "3V3") (class "Default")
      (node (ref "C1") (pin "2") (pinfunction "2_2") (pintype "input"))
      (node (ref "C15") (pin "2") (pinfunction "2_2") (pintype "input"))
      (node (ref "C18") (pin "2") (pinfunction "2_2") (pintype "input"))
      (node (ref "C19") (pin "2") (pinfunction "2_2") (pintype "input"))
      (node (ref "C2") (pin "2") (pinfunction "2_2") (pintype "input"))
      (node (ref "C20") (pin "2") (pinfunction "2_2") (pintype "input"))
      (node (ref "C23") (pin "2") (pinfunction "2_2") (pintype "input"))
      (node (ref "C25") (pin "2") (pinfunction "2_2") (pintype "input"))
      (node (ref "C27") (pin "2") (pinfunction "2_2") (pintype "input"))
      (node (ref "C29") (pin "2") (pinfunction "2_2") (pintype "input"))
      (node (ref "C3") (pin "2") (pinfunction "2_2") (pintype "input"))
      (node (ref "C4") (pin "2") (pinfunction "2_2") (pintype "input"))
      (node (ref "C5") (pin "2") (pinfunction "2_2") (pintype "input"))
      (node (ref "C6") (pin "2") (pinfunction "2_2") (pintype "input"))
      (node (ref "C7") (pin "2") (pinfunction "2_2") (pintype "input"))
      (node (ref "C8") (pin "2") (pinfunction "2_2") (pintype "input"))
      (node (ref "L1") (pin "2") (pinfunction "2_2") (pintype "input"))
      (node (ref "L2") (pin "1") (pinfunction "1_1") (pintype "input"))
      (node (ref "LED3") (pin "2") (pinfunction "A_2") (pintype "input"))
      (node (ref "R10") (pin "1") (pinfunction "1_1") (pintype "input"))
      (node (ref "R11") (pin "2") (pinfunction "2_2") (pintype "input"))
      (node (ref "R12") (pin "2") (pinfunction "2_2") (pintype "input"))
      (node (ref "R14") (pin "2") (pinfunction "2_2") (pintype "input"))
      (node (ref "R16") (pin "2") (pinfunction "2_2") (pintype "input"))
      (node (ref "R18") (pin "2") (pinfunction "2_2") (pintype "input"))
      (node (ref "R3") (pin "1") (pinfunction "1_1") (pintype "input"))
      (node (ref "R4") (pin "1") (pinfunction "1_1") (pintype "input"))
      (node (ref "R5") (pin "2") (pinfunction "2_2") (pintype "input"))
      (node (ref "R8") (pin "1") (pinfunction "1_1") (pintype "input"))
      (node (ref "U1") (pin "20") (pinfunction "VCCIO_20") (pintype "input"))
      (node (ref "U1") (pin "31") (pinfunction "VCCIO_31") (pintype "input"))
      (node (ref "U1") (pin "42") (pinfunction "VCCIO_42") (pintype "input"))
      (node (ref "U1") (pin "50") (pinfunction "VREGIN_50") (pintype "input"))
      (node (ref "U1") (pin "56") (pinfunction "VCCIO_56") (pintype "input"))
      (node (ref "U10") (pin "1") (pinfunction "VCCA_1") (pintype "unspecified"))
      (node (ref "U3") (pin "5") (pinfunction "OUT_5") (pintype "input"))
      (node (ref "U4") (pin "6") (pinfunction "VCC_6") (pintype "input"))
      (node (ref "U5") (pin "1") (pinfunction "VCCA_1") (pintype "unspecified"))
      (node (ref "U6") (pin "1") (pinfunction "VCCA_1") (pintype "unspecified"))
      (node (ref "U7") (pin "1") (pinfunction "VCCA_1") (pintype "unspecified"))
      (node (ref "U8") (pin "1") (pinfunction "VCCA_1") (pintype "unspecified"))
      (node (ref "U9") (pin "1") (pinfunction "VCCA_1") (pintype "unspecified"))
    )
    (net (code "27") (name "GND") (class "Default")
      (node (ref "C1") (pin "1") (pinfunction "1_1") (pintype "input"))
      (node (ref "C10") (pin "1") (pinfunction "1_1") (pintype "input"))
      (node (ref "C11") (pin "1") (pinfunction "1_1") (pintype "input"))
      (node (ref "C12") (pin "1") (pinfunction "1_1") (pintype "input"))
      (node (ref "C13") (pin "2") (pinfunction "2_2") (pintype "input"))
      (node (ref "C14") (pin "2") (pinfunction "2_2") (pintype "input"))
      (node (ref "C15") (pin "1") (pinfunction "1_1") (pintype "input"))
      (node (ref "C16") (pin "2") (pinfunction "GND_2") (pintype "input"))
      (node (ref "C16") (pin "4") (pinfunction "GND_4") (pintype "input"))
      (node (ref "C17") (pin "1") (pinfunction "1_1") (pintype "input"))
      (node (ref "C18") (pin "1") (pinfunction "1_1") (pintype "input"))
      (node (ref "C19") (pin "1") (pinfunction "1_1") (pintype "input"))
      (node (ref "C2") (pin "1") (pinfunction "1_1") (pintype "input"))
      (node (ref "C20") (pin "1") (pinfunction "1_1") (pintype "input"))
      (node (ref "C21") (pin "1") (pinfunction "1_1") (pintype "input"))
      (node (ref "C22") (pin "1") (pinfunction "1_1") (pintype "input"))
      (node (ref "C23") (pin "1") (pinfunction "1_1") (pintype "input"))
      (node (ref "C24") (pin "1") (pinfunction "1_1") (pintype "input"))
      (node (ref "C25") (pin "1") (pinfunction "1_1") (pintype "input"))
      (node (ref "C26") (pin "1") (pinfunction "1_1") (pintype "input"))
      (node (ref "C27") (pin "1") (pinfunction "1_1") (pintype "input"))
      (node (ref "C28") (pin "1") (pinfunction "1_1") (pintype "input"))
      (node (ref "C29") (pin "1") (pinfunction "1_1") (pintype "input"))
      (node (ref "C3") (pin "1") (pinfunction "1_1") (pintype "input"))
      (node (ref "C30") (pin "1") (pinfunction "1_1") (pintype "input"))
      (node (ref "C32") (pin "1") (pinfunction "1_1") (pintype "input"))
      (node (ref "C33") (pin "1") (pinfunction "1_1") (pintype "input"))
      (node (ref "C4") (pin "1") (pinfunction "1_1") (pintype "input"))
      (node (ref "C5") (pin "1") (pinfunction "1_1") (pintype "input"))
      (node (ref "C6") (pin "1") (pinfunction "1_1") (pintype "input"))
      (node (ref "C7") (pin "1") (pinfunction "1_1") (pintype "input"))
      (node (ref "C8") (pin "1") (pinfunction "1_1") (pintype "input"))
      (node (ref "C9") (pin "1") (pinfunction "1_1") (pintype "input"))
      (node (ref "D1") (pin "1") (pinfunction "C_1") (pintype "unspecified"))
      (node (ref "D2") (pin "1") (pinfunction "C_1") (pintype "unspecified"))
      (node (ref "D3") (pin "1") (pinfunction "C_1") (pintype "unspecified"))
      (node (ref "D4") (pin "1") (pinfunction "C_1") (pintype "unspecified"))
      (node (ref "D5") (pin "1") (pinfunction "C_1") (pintype "unspecified"))
      (node (ref "D6") (pin "1") (pinfunction "C_1") (pintype "unspecified"))
      (node (ref "D7") (pin "1") (pinfunction "C_1") (pintype "unspecified"))
      (node (ref "H1") (pin "10") (pinfunction "10_10") (pintype "unspecified"))
      (node (ref "H1") (pin "2") (pinfunction "2_2") (pintype "unspecified"))
      (node (ref "H2") (pin "4") (pinfunction "4_4") (pintype "unspecified"))
      (node (ref "Q1") (pin "2") (pinfunction "S_2") (pintype "unspecified"))
      (node (ref "R1") (pin "1") (pinfunction "1_1") (pintype "input"))
      (node (ref "R15") (pin "2") (pinfunction "2_2") (pintype "input"))
      (node (ref "R17") (pin "2") (pinfunction "2_2") (pintype "input"))
      (node (ref "R2") (pin "1") (pinfunction "1_1") (pintype "input"))
      (node (ref "R20") (pin "1") (pinfunction "1_1") (pintype "input"))
      (node (ref "R7") (pin "2") (pinfunction "2_2") (pintype "input"))
      (node (ref "R9") (pin "1") (pinfunction "1_1") (pintype "input"))
      (node (ref "U1") (pin "1") (pinfunction "GND_1") (pintype "input"))
      (node (ref "U1") (pin "10") (pinfunction "AGND_10") (pintype "input"))
      (node (ref "U1") (pin "11") (pinfunction "GND_11") (pintype "input"))
      (node (ref "U1") (pin "13") (pinfunction "TEST_13") (pintype "input"))
      (node (ref "U1") (pin "15") (pinfunction "GND_15") (pintype "input"))
      (node (ref "U1") (pin "25") (pinfunction "GND_25") (pintype "input"))
      (node (ref "U1") (pin "35") (pinfunction "GND_35") (pintype "input"))
      (node (ref "U1") (pin "47") (pinfunction "GND_47") (pintype "input"))
      (node (ref "U1") (pin "5") (pinfunction "GND_5") (pintype "input"))
      (node (ref "U1") (pin "51") (pinfunction "GND_51") (pintype "input"))
      (node (ref "U1") (pin "65") (pinfunction "EP_65") (pintype "input"))
      (node (ref "U10") (pin "2") (pinfunction "GND_2") (pintype "unspecified"))
      (node (ref "U2") (pin "5") (pinfunction "GND_5") (pintype "input"))
      (node (ref "U2") (pin "7") (pinfunction "EP_7") (pintype "input"))
      (node (ref "U3") (pin "2") (pinfunction "GND_2") (pintype "input"))
      (node (ref "U4") (pin "2") (pinfunction "VSS_2") (pintype "input"))
      (node (ref "U5") (pin "2") (pinfunction "GND_2") (pintype "unspecified"))
      (node (ref "U6") (pin "2") (pinfunction "GND_2") (pintype "unspecified"))
      (node (ref "U7") (pin "2") (pinfunction "GND_2") (pintype "unspecified"))
      (node (ref "U8") (pin "2") (pinfunction "GND_2") (pintype "unspecified"))
      (node (ref "U9") (pin "2") (pinfunction "GND_2") (pintype "unspecified"))
      (node (ref "USB1") (pin "1") (pinfunction "GND_1") (pintype "unspecified"))
      (node (ref "USB1") (pin "12") (pinfunction "GND_12") (pintype "unspecified"))
      (node (ref "USB1") (pin "13") (pinfunction "SHELL_13") (pintype "unspecified"))
      (node (ref "USB1") (pin "14") (pinfunction "SHELL_14") (pintype "unspecified"))
      (node (ref "USB1") (pin "15") (pinfunction "SHELL_15") (pintype "unspecified"))
      (node (ref "USB1") (pin "16") (pinfunction "SHELL_16") (pintype "unspecified"))
      (node (ref "X1") (pin "2") (pinfunction "GND_2") (pintype "input"))
      (node (ref "X1") (pin "4") (pinfunction "GND_4") (pintype "input"))
    )
    (net (code "28") (name "Net-(C16-IN)") (class "Default")
      (node (ref "C14") (pin "1") (pinfunction "1_1") (pintype "input"))
      (node (ref "C16") (pin "1") (pinfunction "IN_1") (pintype "input"))
      (node (ref "U3") (pin "1") (pinfunction "IN_1") (pintype "input"))
      (node (ref "U3") (pin "3") (pinfunction "EN_3") (pintype "input"))
    )
    (net (code "29") (name "Net-(LED1-A)") (class "Default")
      (node (ref "LED1") (pin "2") (pinfunction "A_2") (pintype "input"))
      (node (ref "R5") (pin "1") (pinfunction "1_1") (pintype "input"))
    )
    (net (code "30") (name "Net-(LED2-A)") (class "Default")
      (node (ref "LED2") (pin "2") (pinfunction "A_2") (pintype "input"))
      (node (ref "R8") (pin "2") (pinfunction "2_2") (pintype "input"))
    )
    (net (code "31") (name "Net-(LED3-C)") (class "Default")
      (node (ref "LED3") (pin "1") (pinfunction "C_1") (pintype "input"))
      (node (ref "R19") (pin "2") (pinfunction "2_2") (pintype "input"))
    )
    (net (code "32") (name "Net-(Q1-D)") (class "Default")
      (node (ref "Q1") (pin "3") (pinfunction "D_3") (pintype "unspecified"))
      (node (ref "R19") (pin "1") (pinfunction "1_1") (pintype "input"))
    )
    (net (code "33") (name "Net-(U1-REF)") (class "Default")
      (node (ref "R9") (pin "2") (pinfunction "2_2") (pintype "input"))
      (node (ref "U1") (pin "6") (pinfunction "REF_6") (pintype "input"))
    )
    (net (code "34") (name "Net-(U1-RESET#)") (class "Default")
      (node (ref "R10") (pin "2") (pinfunction "2_2") (pintype "input"))
      (node (ref "U1") (pin "14") (pinfunction "RESET#_14") (pintype "input"))
    )
    (net (code "35") (name "Net-(U1-VPHY)") (class "Default")
      (node (ref "L2") (pin "2") (pinfunction "2_2") (pintype "input"))
      (node (ref "U1") (pin "4") (pinfunction "VPHY_4") (pintype "input"))
    )
    (net (code "36") (name "Net-(U1-VPLL)") (class "Default")
      (node (ref "L1") (pin "1") (pinfunction "1_1") (pintype "input"))
      (node (ref "U1") (pin "9") (pinfunction "VPLL_9") (pintype "input"))
    )
    (net (code "37") (name "Net-(U2-EN)") (class "Default")
      (node (ref "R6") (pin "1") (pinfunction "1_1") (pintype "input"))
      (node (ref "U2") (pin "4") (pinfunction "EN_4") (pintype "input"))
    )
    (net (code "38") (name "Net-(U2-ILIM)") (class "Default")
      (node (ref "R7") (pin "1") (pinfunction "1_1") (pintype "input"))
      (node (ref "U2") (pin "2") (pinfunction "ILIM_2") (pintype "input"))
    )
    (net (code "39") (name "Net-(U5-DIR)") (class "Default")
      (node (ref "R11") (pin "1") (pinfunction "1_1") (pintype "input"))
      (node (ref "U5") (pin "5") (pinfunction "DIR_5") (pintype "unspecified"))
    )
    (net (code "40") (name "Net-(U6-DIR)") (class "Default")
      (node (ref "R12") (pin "1") (pinfunction "1_1") (pintype "input"))
      (node (ref "U6") (pin "5") (pinfunction "DIR_5") (pintype "unspecified"))
    )
    (net (code "41") (name "Net-(U7-DIR)") (class "Default")
      (node (ref "R14") (pin "1") (pinfunction "1_1") (pintype "input"))
      (node (ref "U7") (pin "5") (pinfunction "DIR_5") (pintype "unspecified"))
    )
    (net (code "42") (name "Net-(U8-DIR)") (class "Default")
      (node (ref "R15") (pin "1") (pinfunction "1_1") (pintype "input"))
      (node (ref "U8") (pin "5") (pinfunction "DIR_5") (pintype "unspecified"))
    )
    (net (code "43") (name "Net-(U9-DIR)") (class "Default")
      (node (ref "R17") (pin "1") (pinfunction "1_1") (pintype "input"))
      (node (ref "U9") (pin "5") (pinfunction "DIR_5") (pintype "unspecified"))
    )
    (net (code "44") (name "Net-(U10-DIR)") (class "Default")
      (node (ref "R18") (pin "1") (pinfunction "1_1") (pintype "input"))
      (node (ref "U10") (pin "5") (pinfunction "DIR_5") (pintype "unspecified"))
    )
    (net (code "45") (name "USB_5V") (class "Default")
      (node (ref "C17") (pin "2") (pinfunction "2_2") (pintype "input"))
      (node (ref "R6") (pin "2") (pinfunction "2_2") (pintype "input"))
      (node (ref "TP2") (pin "1") (pinfunction "1_1") (pintype "input"))
      (node (ref "U2") (pin "6") (pinfunction "IN_6") (pintype "input"))
      (node (ref "USB1") (pin "11") (pinfunction "VBUS_11") (pintype "unspecified"))
      (node (ref "USB1") (pin "2") (pinfunction "VBUS_2") (pintype "unspecified"))
    )
    (net (code "46") (name "VCORE") (class "Default")
      (node (ref "C10") (pin "2") (pinfunction "2_2") (pintype "input"))
      (node (ref "C11") (pin "2") (pinfunction "2_2") (pintype "input"))
      (node (ref "C12") (pin "2") (pinfunction "2_2") (pintype "input"))
      (node (ref "C13") (pin "1") (pinfunction "1_1") (pintype "input"))
      (node (ref "TP1") (pin "1") (pinfunction "1_1") (pintype "input"))
      (node (ref "U1") (pin "12") (pinfunction "VCORE_12") (pintype "input"))
      (node (ref "U1") (pin "37") (pinfunction "VCORE_37") (pintype "input"))
      (node (ref "U1") (pin "49") (pinfunction "VREGOUT_49") (pintype "input"))
      (node (ref "U1") (pin "64") (pinfunction "VCORE_64") (pintype "input"))
    )
    (net (code "47") (name "VREF_CONN") (class "Default")
      (node (ref "C21") (pin "2") (pinfunction "2_2") (pintype "input"))
      (node (ref "C22") (pin "2") (pinfunction "2_2") (pintype "input"))
      (node (ref "C24") (pin "2") (pinfunction "2_2") (pintype "input"))
      (node (ref "C26") (pin "2") (pinfunction "2_2") (pintype "input"))
      (node (ref "C28") (pin "2") (pinfunction "2_2") (pintype "input"))
      (node (ref "C30") (pin "2") (pinfunction "2_2") (pintype "input"))
      (node (ref "C9") (pin "2") (pinfunction "2_2") (pintype "input"))
      (node (ref "D7") (pin "2") (pinfunction "A_2") (pintype "unspecified"))
      (node (ref "H1") (pin "4") (pinfunction "4_4") (pintype "unspecified"))
      (node (ref "H2") (pin "1") (pinfunction "1_1") (pintype "unspecified"))
      (node (ref "Q1") (pin "1") (pinfunction "G_1") (pintype "unspecified"))
      (node (ref "R20") (pin "2") (pinfunction "2_2") (pintype "input"))
      (node (ref "U10") (pin "6") (pinfunction "VCCB_6") (pintype "unspecified"))
      (node (ref "U5") (pin "6") (pinfunction "VCCB_6") (pintype "unspecified"))
      (node (ref "U6") (pin "6") (pinfunction "VCCB_6") (pintype "unspecified"))
      (node (ref "U7") (pin "6") (pinfunction "VCCB_6") (pintype "unspecified"))
      (node (ref "U8") (pin "6") (pinfunction "VCCB_6") (pintype "unspecified"))
      (node (ref "U9") (pin "6") (pinfunction "VCCB_6") (pintype "unspecified"))
    )
    (net (code "48") (name "unconnected-(H1-Pad6)") (class "Default")
      (node (ref "H1") (pin "6") (pinfunction "6_6") (pintype "unspecified+no_connect"))
    )
    (net (code "49") (name "unconnected-(H1-Pad7)") (class "Default")
      (node (ref "H1") (pin "7") (pinfunction "7_7") (pintype "unspecified+no_connect"))
    )
    (net (code "50") (name "unconnected-(H1-Pad8)") (class "Default")
      (node (ref "H1") (pin "8") (pinfunction "8_8") (pintype "unspecified+no_connect"))
    )
    (net (code "51") (name "unconnected-(U1-ACBUS0-Pad26)") (class "Default")
      (node (ref "U1") (pin "26") (pinfunction "ACBUS0_26") (pintype "input+no_connect"))
    )
    (net (code "52") (name "unconnected-(U1-ACBUS1-Pad27)") (class "Default")
      (node (ref "U1") (pin "27") (pinfunction "ACBUS1_27") (pintype "input+no_connect"))
    )
    (net (code "53") (name "unconnected-(U1-ACBUS2-Pad28)") (class "Default")
      (node (ref "U1") (pin "28") (pinfunction "ACBUS2_28") (pintype "input+no_connect"))
    )
    (net (code "54") (name "unconnected-(U1-ACBUS3-Pad29)") (class "Default")
      (node (ref "U1") (pin "29") (pinfunction "ACBUS3_29") (pintype "input+no_connect"))
    )
    (net (code "55") (name "unconnected-(U1-ACBUS4-Pad30)") (class "Default")
      (node (ref "U1") (pin "30") (pinfunction "ACBUS4_30") (pintype "input+no_connect"))
    )
    (net (code "56") (name "unconnected-(U1-ACBUS5-Pad32)") (class "Default")
      (node (ref "U1") (pin "32") (pinfunction "ACBUS5_32") (pintype "input+no_connect"))
    )
    (net (code "57") (name "unconnected-(U1-ACBUS6-Pad33)") (class "Default")
      (node (ref "U1") (pin "33") (pinfunction "ACBUS6_33") (pintype "input+no_connect"))
    )
    (net (code "58") (name "unconnected-(U1-ACBUS7-Pad34)") (class "Default")
      (node (ref "U1") (pin "34") (pinfunction "ACBUS7_34") (pintype "input+no_connect"))
    )
    (net (code "59") (name "unconnected-(U1-ADBUS4-Pad21)") (class "Default")
      (node (ref "U1") (pin "21") (pinfunction "ADBUS4_21") (pintype "input+no_connect"))
    )
    (net (code "60") (name "unconnected-(U1-ADBUS5-Pad22)") (class "Default")
      (node (ref "U1") (pin "22") (pinfunction "ADBUS5_22") (pintype "input+no_connect"))
    )
    (net (code "61") (name "unconnected-(U1-ADBUS6-Pad23)") (class "Default")
      (node (ref "U1") (pin "23") (pinfunction "ADBUS6_23") (pintype "input+no_connect"))
    )
    (net (code "62") (name "unconnected-(U1-ADBUS7-Pad24)") (class "Default")
      (node (ref "U1") (pin "24") (pinfunction "ADBUS7_24") (pintype "input+no_connect"))
    )
    (net (code "63") (name "unconnected-(U1-BCBUS0-Pad48)") (class "Default")
      (node (ref "U1") (pin "48") (pinfunction "BCBUS0_48") (pintype "input+no_connect"))
    )
    (net (code "64") (name "unconnected-(U1-BCBUS1-Pad52)") (class "Default")
      (node (ref "U1") (pin "52") (pinfunction "BCBUS1_52") (pintype "input+no_connect"))
    )
    (net (code "65") (name "unconnected-(U1-BCBUS2-Pad53)") (class "Default")
      (node (ref "U1") (pin "53") (pinfunction "BCBUS2_53") (pintype "input+no_connect"))
    )
    (net (code "66") (name "unconnected-(U1-BCBUS5-Pad57)") (class "Default")
      (node (ref "U1") (pin "57") (pinfunction "BCBUS5_57") (pintype "input+no_connect"))
    )
    (net (code "67") (name "unconnected-(U1-BCBUS6-Pad58)") (class "Default")
      (node (ref "U1") (pin "58") (pinfunction "BCBUS6_58") (pintype "input+no_connect"))
    )
    (net (code "68") (name "unconnected-(U1-BCBUS7-Pad59)") (class "Default")
      (node (ref "U1") (pin "59") (pinfunction "BCBUS7_59") (pintype "input+no_connect"))
    )
    (net (code "69") (name "unconnected-(U1-BDBUS2-Pad40)") (class "Default")
      (node (ref "U1") (pin "40") (pinfunction "BDBUS2_40") (pintype "input+no_connect"))
    )
    (net (code "70") (name "unconnected-(U1-BDBUS3-Pad41)") (class "Default")
      (node (ref "U1") (pin "41") (pinfunction "BDBUS3_41") (pintype "input+no_connect"))
    )
    (net (code "71") (name "unconnected-(U1-BDBUS4-Pad43)") (class "Default")
      (node (ref "U1") (pin "43") (pinfunction "BDBUS4_43") (pintype "input+no_connect"))
    )
    (net (code "72") (name "unconnected-(U1-BDBUS5-Pad44)") (class "Default")
      (node (ref "U1") (pin "44") (pinfunction "BDBUS5_44") (pintype "input+no_connect"))
    )
    (net (code "73") (name "unconnected-(U1-BDBUS6-Pad45)") (class "Default")
      (node (ref "U1") (pin "45") (pinfunction "BDBUS6_45") (pintype "input+no_connect"))
    )
    (net (code "74") (name "unconnected-(U1-BDBUS7-Pad46)") (class "Default")
      (node (ref "U1") (pin "46") (pinfunction "BDBUS7_46") (pintype "input+no_connect"))
    )
    (net (code "75") (name "unconnected-(U1-PWREN#-Pad60)") (class "Default")
      (node (ref "U1") (pin "60") (pinfunction "PWREN#_60") (pintype "input+no_connect"))
    )
    (net (code "76") (name "unconnected-(U1-SUSPEND#-Pad36)") (class "Default")
      (node (ref "U1") (pin "36") (pinfunction "SUSPEND#_36") (pintype "input+no_connect"))
    )
    (net (code "77") (name "unconnected-(U2-FAULT#-Pad3)") (class "Default")
      (node (ref "U2") (pin "3") (pinfunction "FAULT#_3") (pintype "input+no_connect"))
    )
    (net (code "78") (name "unconnected-(U3-NC-Pad4)") (class "Default")
      (node (ref "U3") (pin "4") (pinfunction "NC_4") (pintype "input+no_connect"))
    )
    (net (code "79") (name "unconnected-(USB1-SBU1-Pad9)") (class "Default")
      (node (ref "USB1") (pin "9") (pinfunction "SBU1_9") (pintype "unspecified+no_connect"))
    )
    (net (code "80") (name "unconnected-(USB1-SBU2-Pad3)") (class "Default")
      (node (ref "USB1") (pin "3") (pinfunction "SBU2_3") (pintype "unspecified+no_connect"))
    )
  )
)
